# SW8-AcousticsPowerBoard.net
KiCad netlist of a schematic drawn in Altium Designer
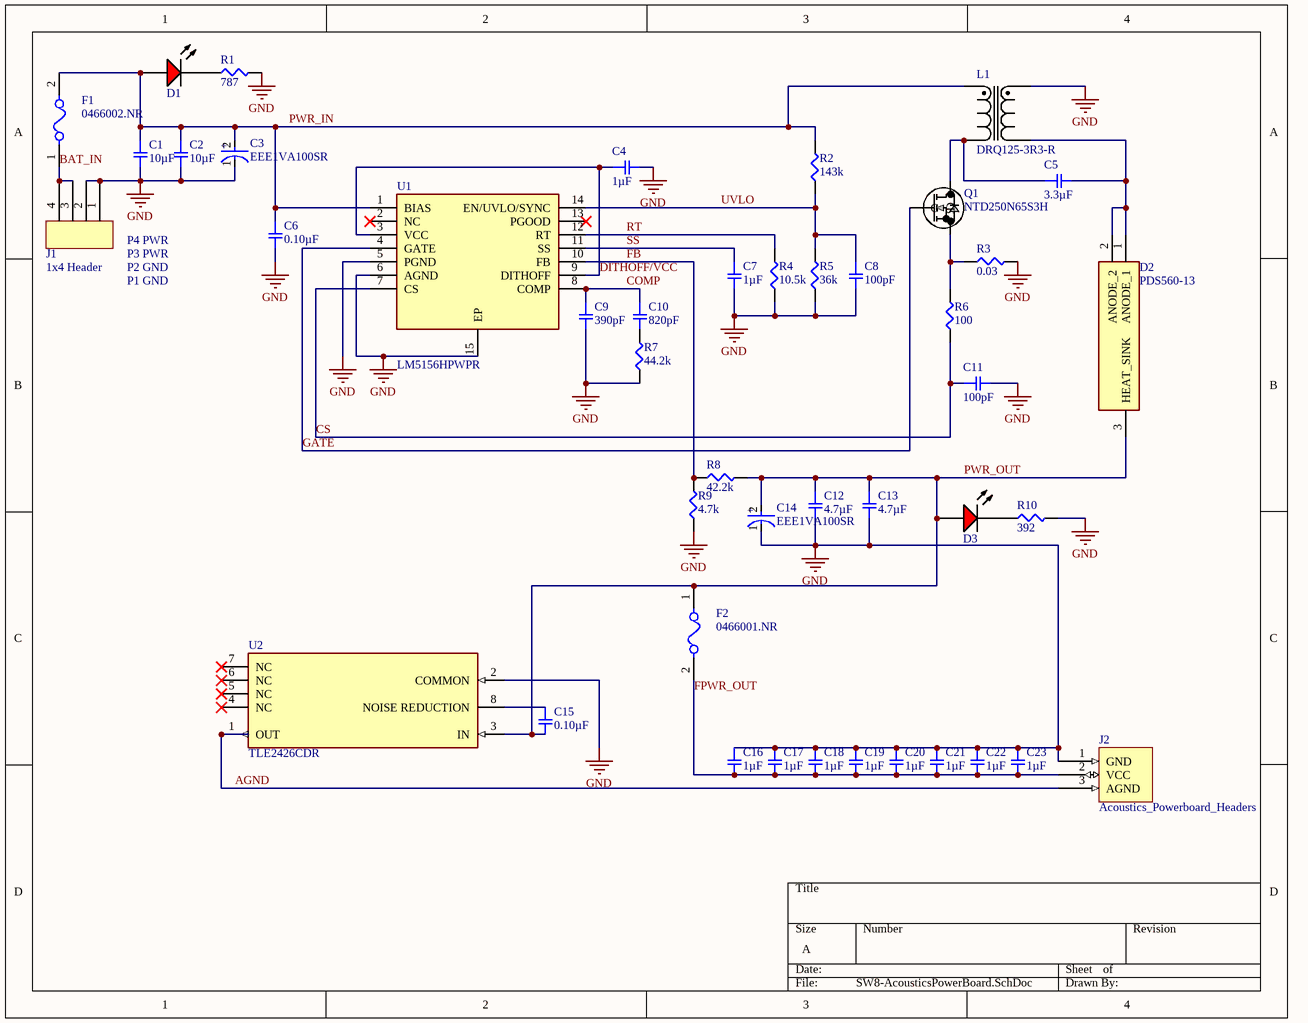
[diagram p0: SW8-AcousticsPowerBoard.SchDoc]

(export (version "E")
  (design (tool "Eeschema 10.0.6"))
  (components
    (comp (ref "C1")
      (value "10µF")
      (footprint "SMD-0805C")
      (description "CAP CER 10UF 25V X5R 0805")
      (fields
        (field (name "DIGI-KEY PART NUMBER") "490-7207-1-ND")
        (field (name "PART NUMBER") "GRM219R61E106KA12D")
      )
      (libsource (lib "capacitor_murata_0805") (part "GRM219R61E106KA12D"))
    )
    (comp (ref "C2")
      (value "10µF")
      (footprint "SMD-0805C")
      (description "CAP CER 10UF 25V X5R 0805")
      (fields
        (field (name "DIGI-KEY PART NUMBER") "490-7207-1-ND")
        (field (name "PART NUMBER") "GRM219R61E106KA12D")
      )
      (libsource (lib "capacitor_murata_0805") (part "GRM219R61E106KA12D"))
    )
    (comp (ref "C3")
      (value "EEE1VA100SR")
      (footprint "FP-SC-MFG")
      (description "CAP ALUM 10UF 20% 35V SMD")
      (fields (field (name "TOLERANCE") "20%") (field (name "VOLTAGE") "35V"))
      (libsource (lib "Altium Content Vault") (part "203bc49f2ac43e59fd269a8c329ed05"))
    )
    (comp (ref "C4")
      (value "1µF")
      (footprint "SMD-0805C")
      (description "CAP CER 1UF 25V X7R 0805")
      (fields
        (field (name "DIGI-KEY PART NUMBER") "490-5802-1-ND")
        (field (name "PART NUMBER") "GCJ21BR71E105KA12L")
      )
      (libsource (lib "capacitor_murata_0805") (part "GCJ21BR71E105KA12L"))
    )
    (comp (ref "C5")
      (value "3.3µF")
      (footprint "SMD-0805C")
      (description "CAP CER 3.3UF 25V X5R 0805")
      (fields
        (field (name "DIGI-KEY PART NUMBER") "490-8313-1-ND")
        (field (name "PART NUMBER") "GRM21BR61E335KA12L")
      )
      (libsource (lib "capacitor_murata_0805") (part "GRM21BR61E335KA12L"))
    )
    (comp (ref "C6")
      (value "0.10µF")
      (footprint "SMD-0805C")
      (description "CAP CER 0.1UF 50V X7R 0805")
      (fields
        (field (name "DIGI-KEY PART NUMBER") "490-11955-1-ND")
        (field (name "PART NUMBER") "GCD21BR71H104KA01L")
      )
      (libsource (lib "capacitor_murata_0805") (part "GCD21BR71H104KA01L"))
    )
    (comp (ref "C7")
      (value "1µF")
      (footprint "SMD-0805C")
      (description "CAP CER 1UF 25V X7R 0805")
      (fields
        (field (name "DIGI-KEY PART NUMBER") "490-5802-1-ND")
        (field (name "PART NUMBER") "GCJ21BR71E105KA12L")
      )
      (libsource (lib "capacitor_murata_0805") (part "GCJ21BR71E105KA12L"))
    )
    (comp (ref "C8")
      (value "100pF")
      (footprint "SMD-0805C")
      (description "CAP CER 100PF 50V NP0 0805")
      (fields
        (field (name "DIGI-KEY PART NUMBER") "490-8031-1-ND")
        (field (name "PART NUMBER") "GCM2165C1H101JA16D")
      )
      (libsource (lib "capacitor_murata_0805") (part "GCM2165C1H101JA16D"))
    )
    (comp (ref "C9")
      (value "390pF")
      (footprint "SMD-0805C")
      (description "CAP CER 390PF 50V NP0 0805")
      (fields
        (field (name "DIGI-KEY PART NUMBER") "490-11547-1-ND")
        (field (name "PART NUMBER") "GRM2165C1H391JA01D")
      )
      (libsource (lib "capacitor_murata_0805") (part "GRM2165C1H391JA01D"))
    )
    (comp (ref "C10")
      (value "820pF")
      (footprint "SMD-0805C")
      (description "CAP CER 820PF 50V NP0 0805")
      (fields
        (field (name "DIGI-KEY PART NUMBER") "490-11551-1-ND")
        (field (name "PART NUMBER") "GRM2165C1H821JA01D")
      )
      (libsource (lib "capacitor_murata_0805") (part "GRM2165C1H821JA01D"))
    )
    (comp (ref "C11")
      (value "100pF")
      (footprint "SMD-0805C")
      (description "CAP CER 100PF 50V NP0 0805")
      (fields
        (field (name "DIGI-KEY PART NUMBER") "490-8031-1-ND")
        (field (name "PART NUMBER") "GCM2165C1H101JA16D")
      )
      (libsource (lib "capacitor_murata_0805") (part "GCM2165C1H101JA16D"))
    )
    (comp (ref "C12")
      (value "4.7µF")
      (footprint "SMD-0805C")
      (description "CAP CER 4.7UF 50V X7S 0805")
      (fields
        (field (name "DIGI-KEY PART NUMBER") "490-12757-1-ND")
        (field (name "PART NUMBER") "GRM21BC71H475KE11L")
      )
      (libsource (lib "capacitor_murata_0805") (part "GRM21BC71H475KE11L"))
    )
    (comp (ref "C13")
      (value "4.7µF")
      (footprint "SMD-0805C")
      (description "CAP CER 4.7UF 50V X7S 0805")
      (fields
        (field (name "DIGI-KEY PART NUMBER") "490-12757-1-ND")
        (field (name "PART NUMBER") "GRM21BC71H475KE11L")
      )
      (libsource (lib "capacitor_murata_0805") (part "GRM21BC71H475KE11L"))
    )
    (comp (ref "C14")
      (value "EEE1VA100SR")
      (footprint "FP-SC-MFG")
      (description "CAP ALUM 10UF 20% 35V SMD")
      (fields (field (name "TOLERANCE") "20%") (field (name "VOLTAGE") "35V"))
      (libsource (lib "Altium Content Vault") (part "203bc49f2ac43e59fd269a8c329ed05"))
    )
    (comp (ref "C15")
      (value "0.10µF")
      (footprint "SMD-0805C")
      (description "CAP CER 0.1UF 50V X7R 0805")
      (fields
        (field (name "DIGI-KEY PART NUMBER") "490-11955-1-ND")
        (field (name "PART NUMBER") "GCD21BR71H104KA01L")
      )
      (libsource (lib "capacitor_murata_0805") (part "GCD21BR71H104KA01L"))
    )
    (comp (ref "C16")
      (value "1µF")
      (footprint "SMD-0805C")
      (description "CAP CER 1UF 50V X7R 0805")
      (fields
        (field (name "DIGI-KEY PART NUMBER") "490-10667-1-ND")
        (field (name "PART NUMBER") "GCJ21BR71H105KA01L")
      )
      (libsource (lib "capacitor_murata_0805") (part "GCJ21BR71H105KA01L"))
    )
    (comp (ref "C17")
      (value "1µF")
      (footprint "SMD-0805C")
      (description "CAP CER 1UF 50V X7R 0805")
      (fields
        (field (name "DIGI-KEY PART NUMBER") "490-10667-1-ND")
        (field (name "PART NUMBER") "GCJ21BR71H105KA01L")
      )
      (libsource (lib "capacitor_murata_0805") (part "GCJ21BR71H105KA01L"))
    )
    (comp (ref "C18")
      (value "1µF")
      (footprint "SMD-0805C")
      (description "CAP CER 1UF 50V X7R 0805")
      (fields
        (field (name "DIGI-KEY PART NUMBER") "490-10667-1-ND")
        (field (name "PART NUMBER") "GCJ21BR71H105KA01L")
      )
      (libsource (lib "capacitor_murata_0805") (part "GCJ21BR71H105KA01L"))
    )
    (comp (ref "C19")
      (value "1µF")
      (footprint "SMD-0805C")
      (description "CAP CER 1UF 50V X7R 0805")
      (fields
        (field (name "DIGI-KEY PART NUMBER") "490-10667-1-ND")
        (field (name "PART NUMBER") "GCJ21BR71H105KA01L")
      )
      (libsource (lib "capacitor_murata_0805") (part "GCJ21BR71H105KA01L"))
    )
    (comp (ref "C20")
      (value "1µF")
      (footprint "SMD-0805C")
      (description "CAP CER 1UF 50V X7R 0805")
      (fields
        (field (name "DIGI-KEY PART NUMBER") "490-10667-1-ND")
        (field (name "PART NUMBER") "GCJ21BR71H105KA01L")
      )
      (libsource (lib "capacitor_murata_0805") (part "GCJ21BR71H105KA01L"))
    )
    (comp (ref "C21")
      (value "1µF")
      (footprint "SMD-0805C")
      (description "CAP CER 1UF 50V X7R 0805")
      (fields
        (field (name "DIGI-KEY PART NUMBER") "490-10667-1-ND")
        (field (name "PART NUMBER") "GCJ21BR71H105KA01L")
      )
      (libsource (lib "capacitor_murata_0805") (part "GCJ21BR71H105KA01L"))
    )
    (comp (ref "C22")
      (value "1µF")
      (footprint "SMD-0805C")
      (description "CAP CER 1UF 50V X7R 0805")
      (fields
        (field (name "DIGI-KEY PART NUMBER") "490-10667-1-ND")
        (field (name "PART NUMBER") "GCJ21BR71H105KA01L")
      )
      (libsource (lib "capacitor_murata_0805") (part "GCJ21BR71H105KA01L"))
    )
    (comp (ref "C23")
      (value "1µF")
      (footprint "SMD-0805C")
      (description "CAP CER 1UF 50V X7R 0805")
      (fields
        (field (name "DIGI-KEY PART NUMBER") "490-10667-1-ND")
        (field (name "PART NUMBER") "GCJ21BR71H105KA01L")
      )
      (libsource (lib "capacitor_murata_0805") (part "GCJ21BR71H105KA01L"))
    )
    (comp (ref "D1")
      (value "TLMS1100-GS08")
      (footprint "VISH-TLMX1100_V")
      (description "LED, RED, 2.1 V, -40 to 100 degC, 2-Pin SMD (0603), RoHS, Tape and Reel")
      (fields
        (field (name "MANUFACTURER") "Wurth Elektronics")
        (field (name "MANUFACTURER PART NUMBER") "150080SS75000")
      )
      (libsource (lib "Altium Content Vault") (part "LED-RED-AK-2"))
    )
    (comp (ref "D2")
      (value "PDS560-13")
      (footprint "POWERDI5")
      (description "Diode")
      (libsource (lib "URC_Lib") (part "PDS560-13"))
    )
    (comp (ref "D3")
      (value "TLMS1100-GS08")
      (footprint "VISH-TLMX1100_V")
      (description "LED, RED, 2.1 V, -40 to 100 degC, 2-Pin SMD (0603), RoHS, Tape and Reel")
      (fields
        (field (name "MANUFACTURER") "Wurth Elektronics")
        (field (name "MANUFACTURER PART NUMBER") "150080SS75000")
      )
      (libsource (lib "Altium Content Vault") (part "LED-RED-AK-2"))
    )
    (comp (ref "F1")
      (value "0466002.NR")
      (footprint "FP-0466-MFG")
      (description "FUSE BOARD MNT 2A 63VAC/VDC 1206")
      (fields
        (field (name "OCTOPART") "https://octopart.com/0466002.nr-littelfuse-566006")
        (field (name "MANUFACTURER") "Littelfuse")
      )
      (libsource (lib "Altium Content Vault") (part "5bcf9b9f640e542cf0359d10258e979"))
    )
    (comp (ref "F2")
      (value "0466001.NR")
      (footprint "FP-0466-MFG")
      (description "FUSE BOARD MNT 1A 63VAC/VDC 1206")
      (fields
        (field (name "MANUFACTURER") "Littelfuse Inc")
        (field (name "OCTOPART") "https://octopart.com/0466001.nr-littelfuse-566005")
      )
      (libsource (lib "Altium Content Vault") (part "5bcf9b9f640e542cf0359d10258e979"))
    )
    (comp (ref "J1")
      (value "1x4 Header")
      (footprint "1X4 HEADER")
      (description "CONN HEADER VERT 4POS 2.54MM")
      (fields
        (field (name "MANUFACTURER") "Würth Elektronik")
        (field (name "MANUFACTURER PART NUMBER") "61300411121")
      )
      (libsource (lib "URC_Lib") (part "1X4 Header"))
    )
    (comp (ref "J2")
      (value "Acoustics_Powerboard_Headers")
      (footprint "Acoustics_Powerboard_Headers")
      (libsource (lib "URC_Lib") (part "Acoustics_Powerboard_Headers"))
    )
    (comp (ref "L1")
      (value "DRQ125-3R3-R")
      (footprint "DRQ125")
      (fields (field (name "COPYRIGHT") "Copyright (C) 2022 Ultra Librarian. All rights reserved."))
      (libsource (lib "URC_Lib") (part "DRQ125-3R3-R"))
    )
    (comp (ref "Q1")
      (value "NTD250N65S3H")
      (footprint "TO252_NTD250_ONS")
      (description "No Description Available")
      (fields (field (name "COPYRIGHT") "Copyright (C) 2022 Ultra Librarian. All rights reserved."))
      (libsource (lib "URC_Lib") (part "NTD250N65S3H"))
    )
    (comp (ref "R1")
      (value "787")
      (footprint "SMD-0805-RES")
      (description "RES SMD 787 OHM 1% 1/8W 0805")
      (fields (field (name "PART NUMBER") "ERJ-6ENF7870V") (field (name "DIGI-KEY PART NUMBER") "P787CCT-ND"))
      (libsource (lib "Panasonic_resistor_0805") (part "ERJ-6ENF7870V"))
    )
    (comp (ref "R2")
      (value "143k")
      (footprint "SMD-0805-RES")
      (description "RES SMD 143K OHM 1% 1/8W 0805")
      (fields
        (field (name "PART NUMBER") "ERJ-6ENF1433V")
        (field (name "DIGI-KEY PART NUMBER") "P143KCCT-ND")
      )
      (libsource (lib "Panasonic_resistor_0805") (part "ERJ-6ENF1433V"))
    )
    (comp (ref "R3")
      (value "0.03")
      (footprint "SMD-0805-RES")
      (description "RES SMD 0.03 OHM 1% 1/2W 0805")
      (fields
        (field (name "PART NUMBER") "ERJ-6BWFR030V")
        (field (name "DIGI-KEY PART NUMBER") "P.03AQCT-ND")
      )
      (libsource (lib "Panasonic_resistor_0805") (part "ERJ-6BWFR030V"))
    )
    (comp (ref "R4")
      (value "10.5k")
      (footprint "SMD-0805-RES")
      (description "RES SMD 10.5K OHM 1% 1/8W 0805")
      (fields
        (field (name "PART NUMBER") "ERJ-6ENF1052V")
        (field (name "DIGI-KEY PART NUMBER") "P10.5KCCT-ND")
      )
      (libsource (lib "Panasonic_resistor_0805") (part "ERJ-6ENF1052V"))
    )
    (comp (ref "R5")
      (value "36k")
      (footprint "SMD-0805-RES")
      (description "RES SMD 36K OHM 1% 1/8W 0805")
      (fields
        (field (name "PART NUMBER") "ERJ-6ENF3602V")
        (field (name "DIGI-KEY PART NUMBER") "P36.0KCCT-ND")
      )
      (libsource (lib "Panasonic_resistor_0805") (part "ERJ-6ENF3602V"))
    )
    (comp (ref "R6")
      (value "100")
      (footprint "SMD-0805-RES")
      (description "RES SMD 100 OHM 1% 1/8W 0805")
      (fields (field (name "PART NUMBER") "ERJ-6ENF1000V") (field (name "DIGI-KEY PART NUMBER") "P100CCT-ND"))
      (libsource (lib "Panasonic_resistor_0805") (part "ERJ-6ENF1000V"))
    )
    (comp (ref "R7")
      (value "44.2k")
      (footprint "SMD-0805-RES")
      (description "RES SMD 44.2K OHM 1% 1/8W 0805")
      (fields
        (field (name "PART NUMBER") "ERJ-6ENF4422V")
        (field (name "DIGI-KEY PART NUMBER") "P44.2KCCT-ND")
      )
      (libsource (lib "Panasonic_resistor_0805") (part "ERJ-6ENF4422V"))
    )
    (comp (ref "R8")
      (value "42.2k")
      (footprint "SMD-0805-RES")
      (description "RES SMD 42.2K OHM 1% 1/8W 0805")
      (fields
        (field (name "PART NUMBER") "ERJ-6ENF4222V")
        (field (name "DIGI-KEY PART NUMBER") "P42.2KCCT-ND")
      )
      (libsource (lib "Panasonic_resistor_0805") (part "ERJ-6ENF4222V"))
    )
    (comp (ref "R9")
      (value "4.7k")
      (footprint "SMD-0805-RES")
      (description "RES SMD 4.7K OHM 1% 1/8W 0805")
      (fields
        (field (name "PART NUMBER") "ERJ-6ENF4701V")
        (field (name "DIGI-KEY PART NUMBER") "P4.70KCCT-ND")
      )
      (libsource (lib "Panasonic_resistor_0805") (part "ERJ-6ENF4701V"))
    )
    (comp (ref "R10")
      (value "392")
      (footprint "SMD-0805-RES")
      (description "RES SMD 392 OHM 1% 1/8W 0805")
      (fields (field (name "PART NUMBER") "ERJ-6ENF3920V") (field (name "DIGI-KEY PART NUMBER") "P392CCT-ND"))
      (libsource (lib "Panasonic_resistor_0805") (part "ERJ-6ENF3920V"))
    )
    (comp (ref "U1")
      (value "LM5156HPWPR")
      (footprint "SOP65P640X120-15N")
      (description "Integrated Circuit")
      (libsource (lib "URC_Lib") (part "LM5156HPWPR"))
    )
    (comp (ref "U2")
      (value "TLE2426CDR")
      (footprint "FP-D0008A-IPC_B")
      (description "IC VREF GND REF 20V 1% 8SOIC")
      (fields (field (name "TOLERANCE") "1%"))
      (libsource (lib "Altium Content Vault") (part "6a05ed44ac4318f8a6b310f721958da"))
    )
  )
  (nets
    (net (code "1") (name "/AGND") (class "Default")
      (node (ref "J2") (pin "3") (pinfunction "AGND_3") (pintype "input"))
      (node (ref "U2") (pin "1") (pinfunction "OUT_1") (pintype "output"))
    )
    (net (code "2") (name "/BAT_IN") (class "Default")
      (node (ref "F1") (pin "1") (pinfunction "1_1") (pintype "passive"))
      (node (ref "J1") (pin "3") (pinfunction "3_3") (pintype "passive"))
      (node (ref "J1") (pin "4") (pinfunction "4_4") (pintype "passive"))
    )
    (net (code "3") (name "/COMP") (class "Default")
      (node (ref "C10") (pin "1") (pinfunction "1_1") (pintype "passive"))
      (node (ref "C9") (pin "1") (pinfunction "1_1") (pintype "passive"))
      (node (ref "U1") (pin "8") (pinfunction "COMP_8") (pintype "passive"))
    )
    (net (code "4") (name "/CS") (class "Default")
      (node (ref "C11") (pin "1") (pinfunction "1_1") (pintype "passive"))
      (node (ref "R6") (pin "1") (pinfunction "1_1") (pintype "passive"))
      (node (ref "U1") (pin "7") (pinfunction "CS_7") (pintype "passive"))
    )
    (net (code "5") (name "/DITHOFF{slash}VCC") (class "Default")
      (node (ref "C4") (pin "1") (pinfunction "1_1") (pintype "passive"))
      (node (ref "U1") (pin "3") (pinfunction "VCC_3") (pintype "passive"))
      (node (ref "U1") (pin "9") (pinfunction "DITHOFF_9") (pintype "passive"))
    )
    (net (code "6") (name "/FB") (class "Default")
      (node (ref "R8") (pin "1") (pinfunction "1_1") (pintype "passive"))
      (node (ref "R9") (pin "2") (pinfunction "2_2") (pintype "passive"))
      (node (ref "U1") (pin "10") (pinfunction "FB_10") (pintype "passive"))
    )
    (net (code "7") (name "/FPWR_OUT") (class "Default")
      (node (ref "C16") (pin "2") (pinfunction "2_2") (pintype "passive"))
      (node (ref "C17") (pin "2") (pinfunction "2_2") (pintype "passive"))
      (node (ref "C18") (pin "2") (pinfunction "2_2") (pintype "passive"))
      (node (ref "C19") (pin "2") (pinfunction "2_2") (pintype "passive"))
      (node (ref "C20") (pin "2") (pinfunction "2_2") (pintype "passive"))
      (node (ref "C21") (pin "2") (pinfunction "2_2") (pintype "passive"))
      (node (ref "C22") (pin "2") (pinfunction "2_2") (pintype "passive"))
      (node (ref "C23") (pin "2") (pinfunction "2_2") (pintype "passive"))
      (node (ref "F2") (pin "2") (pinfunction "2_2") (pintype "passive"))
      (node (ref "J2") (pin "2") (pinfunction "VCC_2") (pintype "bidirectional"))
    )
    (net (code "8") (name "/GATE") (class "Default")
      (node (ref "Q1") (pin "1") (pinfunction "G_1") (pintype "passive"))
      (node (ref "U1") (pin "4") (pinfunction "GATE_4") (pintype "passive"))
    )
    (net (code "9") (name "/PWR_IN") (class "Default")
      (node (ref "C1") (pin "1") (pinfunction "1_1") (pintype "passive"))
      (node (ref "C2") (pin "1") (pinfunction "1_1") (pintype "passive"))
      (node (ref "C3") (pin "2") (pinfunction "A_2") (pintype "passive"))
      (node (ref "C6") (pin "1") (pinfunction "1_1") (pintype "passive"))
      (node (ref "D1") (pin "1") (pinfunction "A_1") (pintype "passive"))
      (node (ref "F1") (pin "2") (pinfunction "2_2") (pintype "passive"))
      (node (ref "L1") (pin "1") (pinfunction "1_1") (pintype "passive"))
      (node (ref "R2") (pin "2") (pinfunction "2_2") (pintype "passive"))
      (node (ref "U1") (pin "1") (pinfunction "BIAS_1") (pintype "passive"))
    )
    (net (code "10") (name "/PWR_OUT") (class "Default")
      (node (ref "C12") (pin "1") (pinfunction "1_1") (pintype "passive"))
      (node (ref "C13") (pin "1") (pinfunction "1_1") (pintype "passive"))
      (node (ref "C14") (pin "2") (pinfunction "A_2") (pintype "passive"))
      (node (ref "C15") (pin "2") (pinfunction "2_2") (pintype "passive"))
      (node (ref "D2") (pin "3") (pinfunction "HEAT_SINK_3") (pintype "passive"))
      (node (ref "D3") (pin "1") (pinfunction "A_1") (pintype "passive"))
      (node (ref "F2") (pin "1") (pinfunction "1_1") (pintype "passive"))
      (node (ref "R8") (pin "2") (pinfunction "2_2") (pintype "passive"))
      (node (ref "U2") (pin "3") (pinfunction "IN_3") (pintype "input"))
    )
    (net (code "11") (name "/RT") (class "Default")
      (node (ref "R4") (pin "2") (pinfunction "2_2") (pintype "passive"))
      (node (ref "U1") (pin "12") (pinfunction "RT_12") (pintype "passive"))
    )
    (net (code "12") (name "/SS") (class "Default")
      (node (ref "C7") (pin "1") (pinfunction "1_1") (pintype "passive"))
      (node (ref "U1") (pin "11") (pinfunction "SS_11") (pintype "passive"))
    )
    (net (code "13") (name "/UVLO") (class "Default")
      (node (ref "C8") (pin "1") (pinfunction "1_1") (pintype "passive"))
      (node (ref "R2") (pin "1") (pinfunction "1_1") (pintype "passive"))
      (node (ref "R5") (pin "2") (pinfunction "2_2") (pintype "passive"))
      (node (ref "U1") (pin "14") (pinfunction "EN/UVLO/SYNC_14") (pintype "passive"))
    )
    (net (code "14") (name "GND") (class "Default")
      (node (ref "C1") (pin "2") (pinfunction "2_2") (pintype "passive"))
      (node (ref "C11") (pin "2") (pinfunction "2_2") (pintype "passive"))
      (node (ref "C12") (pin "2") (pinfunction "2_2") (pintype "passive"))
      (node (ref "C13") (pin "2") (pinfunction "2_2") (pintype "passive"))
      (node (ref "C14") (pin "1") (pinfunction "C_1") (pintype "passive"))
      (node (ref "C16") (pin "1") (pinfunction "1_1") (pintype "passive"))
      (node (ref "C17") (pin "1") (pinfunction "1_1") (pintype "passive"))
      (node (ref "C18") (pin "1") (pinfunction "1_1") (pintype "passive"))
      (node (ref "C19") (pin "1") (pinfunction "1_1") (pintype "passive"))
      (node (ref "C2") (pin "2") (pinfunction "2_2") (pintype "passive"))
      (node (ref "C20") (pin "1") (pinfunction "1_1") (pintype "passive"))
      (node (ref "C21") (pin "1") (pinfunction "1_1") (pintype "passive"))
      (node (ref "C22") (pin "1") (pinfunction "1_1") (pintype "passive"))
      (node (ref "C23") (pin "1") (pinfunction "1_1") (pintype "passive"))
      (node (ref "C3") (pin "1") (pinfunction "C_1") (pintype "passive"))
      (node (ref "C4") (pin "2") (pinfunction "2_2") (pintype "passive"))
      (node (ref "C6") (pin "2") (pinfunction "2_2") (pintype "passive"))
      (node (ref "C7") (pin "2") (pinfunction "2_2") (pintype "passive"))
      (node (ref "C8") (pin "2") (pinfunction "2_2") (pintype "passive"))
      (node (ref "C9") (pin "2") (pinfunction "2_2") (pintype "passive"))
      (node (ref "J1") (pin "1") (pinfunction "1_1") (pintype "passive"))
      (node (ref "J1") (pin "2") (pinfunction "2_2") (pintype "passive"))
      (node (ref "J2") (pin "1") (pinfunction "GND_1") (pintype "input"))
      (node (ref "L1") (pin "2") (pinfunction "2_2") (pintype "passive"))
      (node (ref "R1") (pin "2") (pinfunction "2_2") (pintype "passive"))
      (node (ref "R10") (pin "2") (pinfunction "2_2") (pintype "passive"))
      (node (ref "R3") (pin "2") (pinfunction "2_2") (pintype "passive"))
      (node (ref "R4") (pin "1") (pinfunction "1_1") (pintype "passive"))
      (node (ref "R5") (pin "1") (pinfunction "1_1") (pintype "passive"))
      (node (ref "R7") (pin "1") (pinfunction "1_1") (pintype "passive"))
      (node (ref "R9") (pin "1") (pinfunction "1_1") (pintype "passive"))
      (node (ref "U1") (pin "15") (pinfunction "EP_15") (pintype "passive"))
      (node (ref "U1") (pin "5") (pinfunction "PGND_5") (pintype "passive"))
      (node (ref "U1") (pin "6") (pinfunction "AGND_6") (pintype "passive"))
      (node (ref "U2") (pin "2") (pinfunction "COMMON_2") (pintype "input"))
    )
    (net (code "15") (name "Net-(C10-Pad2)") (class "Default")
      (node (ref "C10") (pin "2") (pinfunction "2_2") (pintype "passive"))
      (node (ref "R7") (pin "2") (pinfunction "2_2") (pintype "passive"))
    )
    (net (code "16") (name "Net-(D1-K)") (class "Default")
      (node (ref "D1") (pin "2") (pinfunction "K_2") (pintype "passive"))
      (node (ref "R1") (pin "1") (pinfunction "1_1") (pintype "passive"))
    )
    (net (code "17") (name "Net-(D2-ANODE_1)") (class "Default")
      (node (ref "C5") (pin "2") (pinfunction "2_2") (pintype "passive"))
      (node (ref "D2") (pin "1") (pinfunction "ANODE_1_1") (pintype "passive"))
      (node (ref "D2") (pin "2") (pinfunction "ANODE_2_2") (pintype "passive"))
      (node (ref "L1") (pin "4") (pinfunction "4_4") (pintype "passive"))
    )
    (net (code "18") (name "Net-(D3-K)") (class "Default")
      (node (ref "D3") (pin "2") (pinfunction "K_2") (pintype "passive"))
      (node (ref "R10") (pin "1") (pinfunction "1_1") (pintype "passive"))
    )
    (net (code "19") (name "Net-(Q1-D)") (class "Default")
      (node (ref "C5") (pin "1") (pinfunction "1_1") (pintype "passive"))
      (node (ref "L1") (pin "3") (pinfunction "3_3") (pintype "passive"))
      (node (ref "Q1") (pin "2") (pinfunction "D_2") (pintype "passive"))
    )
    (net (code "20") (name "Net-(Q1-S)") (class "Default")
      (node (ref "Q1") (pin "3") (pinfunction "S_3") (pintype "passive"))
      (node (ref "R3") (pin "1") (pinfunction "1_1") (pintype "passive"))
      (node (ref "R6") (pin "2") (pinfunction "2_2") (pintype "passive"))
    )
    (net (code "21") (name "Net-(U2-NOISE_REDUCTION)") (class "Default")
      (node (ref "C15") (pin "1") (pinfunction "1_1") (pintype "passive"))
      (node (ref "U2") (pin "8") (pinfunction "NOISE_REDUCTION_8") (pintype "passive"))
    )
    (net (code "22") (name "unconnected-(U1-NC-Pad2)") (class "Default")
      (node (ref "U1") (pin "2") (pinfunction "NC_2") (pintype "passive+no_connect"))
    )
    (net (code "23") (name "unconnected-(U1-PGOOD-Pad13)") (class "Default")
      (node (ref "U1") (pin "13") (pinfunction "PGOOD_13") (pintype "passive+no_connect"))
    )
    (net (code "24") (name "unconnected-(U2-NC-Pad4)") (class "Default")
      (node (ref "U2") (pin "4") (pinfunction "NC_4") (pintype "passive+no_connect"))
    )
    (net (code "25") (name "unconnected-(U2-NC-Pad5)") (class "Default")
      (node (ref "U2") (pin "5") (pinfunction "NC_5") (pintype "passive+no_connect"))
    )
    (net (code "26") (name "unconnected-(U2-NC-Pad6)") (class "Default")
      (node (ref "U2") (pin "6") (pinfunction "NC_6") (pintype "passive+no_connect"))
    )
    (net (code "27") (name "unconnected-(U2-NC-Pad7)") (class "Default")
      (node (ref "U2") (pin "7") (pinfunction "NC_7") (pintype "passive+no_connect"))
    )
  )
)
